# w076o.net
KiCad netlist of a schematic drawn in EAGLE
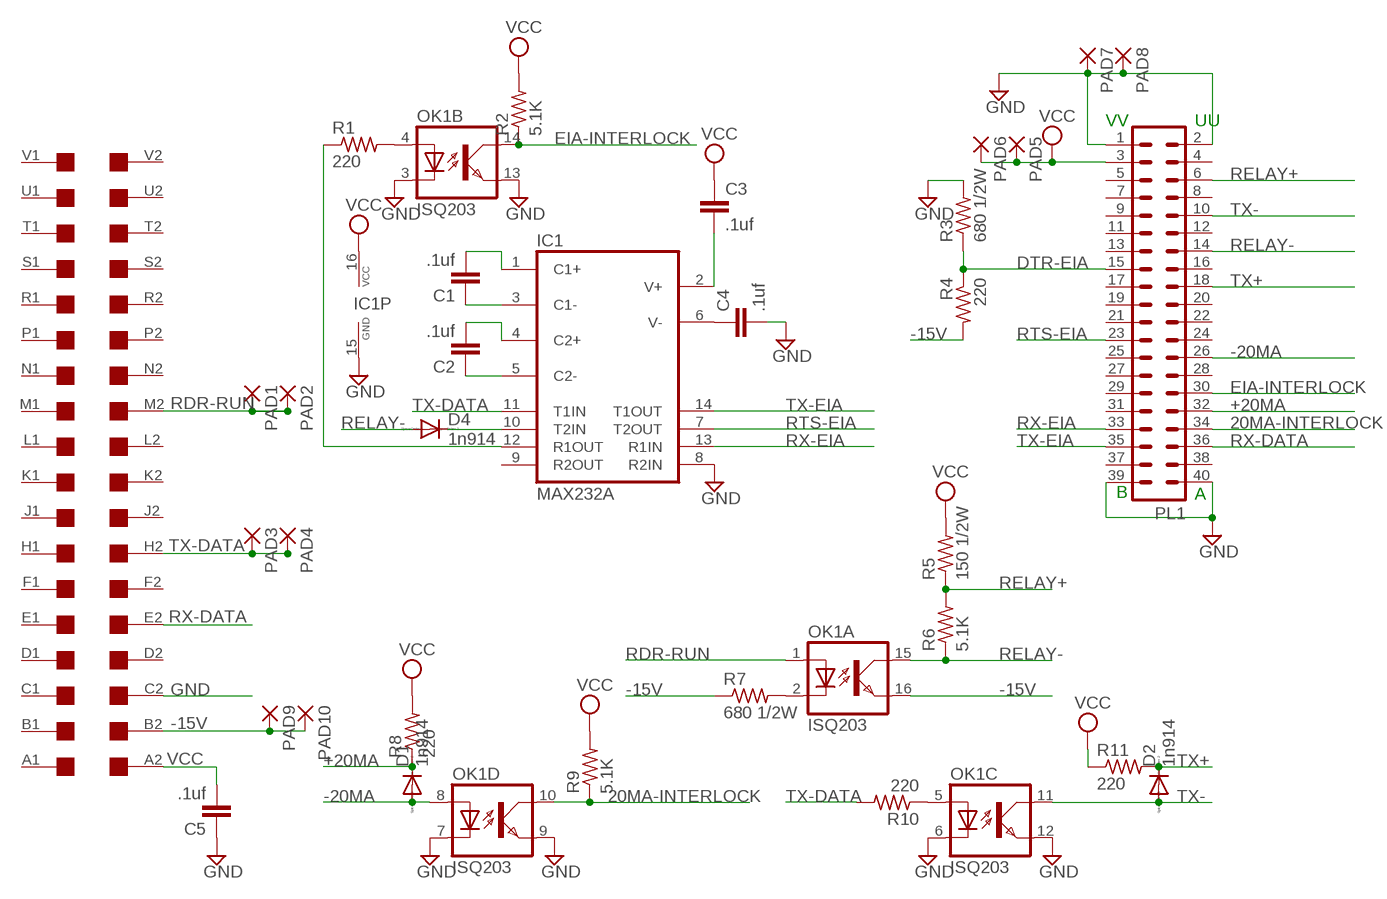
[diagram p0: schematic, sheet 1]

(export (version "E")
  (design (tool "Eeschema 10.0.6"))
  (components
    (comp (ref "C1")
      (value ".1uf")
      (footprint "eagle-import:C050-025X075")
      (libsource (lib "eagle-import") (part "C-EU050-025X075"))
    )
    (comp (ref "C2")
      (value ".1uf")
      (footprint "eagle-import:C050-025X075")
      (libsource (lib "eagle-import") (part "C-EU050-025X075"))
    )
    (comp (ref "C3")
      (value ".1uf")
      (footprint "eagle-import:C050-025X075")
      (libsource (lib "eagle-import") (part "C-EU050-025X075"))
    )
    (comp (ref "C4")
      (value ".1uf")
      (footprint "eagle-import:C050-025X075")
      (libsource (lib "eagle-import") (part "C-EU050-025X075"))
    )
    (comp (ref "C5")
      (value ".1uf")
      (footprint "eagle-import:C050-025X075")
      (libsource (lib "eagle-import") (part "C-EU050-025X075"))
    )
    (comp (ref "D1")
      (value "1n914")
      (footprint "eagle-import:DO41-10")
      (libsource (lib "eagle-import") (part "1N4004"))
    )
    (comp (ref "D2")
      (value "1n914")
      (footprint "eagle-import:DO41-10")
      (libsource (lib "eagle-import") (part "1N4004"))
    )
    (comp (ref "D4")
      (value "1n914")
      (footprint "eagle-import:DO41-10")
      (libsource (lib "eagle-import") (part "1N4004"))
    )
    (comp (ref "IC1")
      (value "MAX232A")
      (footprint "eagle-import:DIL16")
      (fields (field (name "MF") "MAXIM") (field (name "MPN") "MAX232ACPE+"))
      (libsource (lib "eagle-import") (part "MAX232"))
    )
    (comp (ref "OK1")
      (value "ISQ203")
      (footprint "eagle-import:DIL16")
      (fields (field (name "MF") "VISHAY/TELEFUNKEN") (field (name "MPN") "ILQ1"))
      (libsource (lib "eagle-import") (part "ILQ1"))
    )
    (comp (ref "PAD1")
      (value "1,6/0,8")
      (footprint "eagle-import:1,6_0,8")
      (libsource (lib "eagle-import") (part "1,6/0,8"))
    )
    (comp (ref "PAD2")
      (value "1,6/0,8")
      (footprint "eagle-import:1,6_0,8")
      (libsource (lib "eagle-import") (part "1,6/0,8"))
    )
    (comp (ref "PAD3")
      (value "1,6/0,8")
      (footprint "eagle-import:1,6_0,8")
      (libsource (lib "eagle-import") (part "1,6/0,8"))
    )
    (comp (ref "PAD4")
      (value "1,6/0,8")
      (footprint "eagle-import:1,6_0,8")
      (libsource (lib "eagle-import") (part "1,6/0,8"))
    )
    (comp (ref "PAD5")
      (value "1,6/0,8")
      (footprint "eagle-import:1,6_0,8")
      (libsource (lib "eagle-import") (part "1,6/0,8"))
    )
    (comp (ref "PAD6")
      (value "1,6/0,8")
      (footprint "eagle-import:1,6_0,8")
      (libsource (lib "eagle-import") (part "1,6/0,8"))
    )
    (comp (ref "PAD7")
      (value "1,6/0,8")
      (footprint "eagle-import:1,6_0,8")
      (libsource (lib "eagle-import") (part "1,6/0,8"))
    )
    (comp (ref "PAD8")
      (value "1,6/0,8")
      (footprint "eagle-import:1,6_0,8")
      (libsource (lib "eagle-import") (part "1,6/0,8"))
    )
    (comp (ref "PAD9")
      (value "1,6/0,8")
      (footprint "eagle-import:1,6_0,8")
      (libsource (lib "eagle-import") (part "1,6/0,8"))
    )
    (comp (ref "PAD10")
      (value "1,6/0,8")
      (footprint "eagle-import:1,6_0,8")
      (libsource (lib "eagle-import") (part "1,6/0,8"))
    )
    (comp (ref "PL1")
      (value "40H")
      (footprint "eagle-import:40H")
      (libsource (lib "eagle-import") (part "40H"))
    )
    (comp (ref "R1")
      (value "220")
      (footprint "eagle-import:0207_10")
      (libsource (lib "eagle-import") (part "R-US_0207/10"))
    )
    (comp (ref "R2")
      (value "5.1K")
      (footprint "eagle-import:0207_10")
      (libsource (lib "eagle-import") (part "R-US_0207/10"))
    )
    (comp (ref "R3")
      (value "680 1/2W")
      (footprint "eagle-import:0207_12")
      (libsource (lib "eagle-import") (part "R-US_0207/12"))
    )
    (comp (ref "R4")
      (value "220")
      (footprint "eagle-import:0207_10")
      (libsource (lib "eagle-import") (part "R-US_0207/10"))
    )
    (comp (ref "R5")
      (value "150 1/2W")
      (footprint "eagle-import:0207_12")
      (libsource (lib "eagle-import") (part "R-US_0207/12"))
    )
    (comp (ref "R6")
      (value "5.1K")
      (footprint "eagle-import:0207_10")
      (libsource (lib "eagle-import") (part "R-US_0207/10"))
    )
    (comp (ref "R7")
      (value "680 1/2W")
      (footprint "eagle-import:0207_12")
      (libsource (lib "eagle-import") (part "R-US_0207/12"))
    )
    (comp (ref "R8")
      (value "220")
      (footprint "eagle-import:0207_10")
      (libsource (lib "eagle-import") (part "R-US_0207/10"))
    )
    (comp (ref "R9")
      (value "5.1K")
      (footprint "eagle-import:0207_10")
      (libsource (lib "eagle-import") (part "R-US_0207/10"))
    )
    (comp (ref "R10")
      (value "220")
      (footprint "eagle-import:0207_10")
      (libsource (lib "eagle-import") (part "R-US_0207/10"))
    )
    (comp (ref "R11")
      (value "220")
      (footprint "eagle-import:0207_10")
      (libsource (lib "eagle-import") (part "R-US_0207/10"))
    )
    (comp (ref "U$1")
      (value "DEC-FLIPCHIP")
      (footprint "eagle-import:DEC-FLIPCHIP")
      (libsource (lib "eagle-import") (part "DEC-FLIPCHIP"))
    )
  )
  (nets
    (net (code "1") (name "/+20MA") (class "Default")
      (node (ref "D1") (pin "C") (pinfunction "C_C") (pintype "passive"))
      (node (ref "PL1") (pin "32") (pinfunction "32_32") (pintype "passive"))
      (node (ref "R8") (pin "1") (pinfunction "1_1") (pintype "passive"))
    )
    (net (code "2") (name "/-15V") (class "Default")
      (node (ref "OK1") (pin "16") (pinfunction "EMIT_16") (pintype "passive"))
      (node (ref "PAD10") (pin "1") (pinfunction "P_1") (pintype "passive"))
      (node (ref "PAD9") (pin "1") (pinfunction "P_1") (pintype "passive"))
      (node (ref "R4") (pin "2") (pinfunction "2_2") (pintype "passive"))
      (node (ref "R7") (pin "1") (pinfunction "1_1") (pintype "passive"))
      (node (ref "U$1") (pin "B2") (pinfunction "B2_B2") (pintype "passive"))
    )
    (net (code "3") (name "/-20MA") (class "Default")
      (node (ref "D1") (pin "A") (pinfunction "A_A") (pintype "passive"))
      (node (ref "OK1") (pin "8") (pinfunction "A_8") (pintype "passive"))
      (node (ref "PL1") (pin "26") (pinfunction "26_26") (pintype "passive"))
    )
    (net (code "4") (name "/20MA-INTERLOCK") (class "Default")
      (node (ref "OK1") (pin "10") (pinfunction "COL_10") (pintype "passive"))
      (node (ref "PL1") (pin "34") (pinfunction "34_34") (pintype "passive"))
      (node (ref "R9") (pin "1") (pinfunction "1_1") (pintype "passive"))
    )
    (net (code "5") (name "/DTR-EIA") (class "Default")
      (node (ref "PL1") (pin "15") (pinfunction "15_15") (pintype "passive"))
      (node (ref "R3") (pin "1") (pinfunction "1_1") (pintype "passive"))
      (node (ref "R4") (pin "1") (pinfunction "1_1") (pintype "passive"))
    )
    (net (code "6") (name "/EIA-INTERLOCK") (class "Default")
      (node (ref "OK1") (pin "14") (pinfunction "COL_14") (pintype "passive"))
      (node (ref "PL1") (pin "30") (pinfunction "30_30") (pintype "passive"))
      (node (ref "R2") (pin "1") (pinfunction "1_1") (pintype "passive"))
    )
    (net (code "7") (name "/RDR-RUN") (class "Default")
      (node (ref "OK1") (pin "1") (pinfunction "A_1") (pintype "passive"))
      (node (ref "PAD1") (pin "1") (pinfunction "P_1") (pintype "passive"))
      (node (ref "PAD2") (pin "1") (pinfunction "P_1") (pintype "passive"))
      (node (ref "U$1") (pin "M2") (pinfunction "M2_M2") (pintype "passive"))
    )
    (net (code "8") (name "/RELAY+") (class "Default")
      (node (ref "PL1") (pin "6") (pinfunction "6_6") (pintype "passive"))
      (node (ref "R5") (pin "1") (pinfunction "1_1") (pintype "passive"))
      (node (ref "R6") (pin "2") (pinfunction "2_2") (pintype "passive"))
    )
    (net (code "9") (name "/RELAY-") (class "Default")
      (node (ref "D4") (pin "A") (pinfunction "A_A") (pintype "passive"))
      (node (ref "OK1") (pin "15") (pinfunction "COL_15") (pintype "passive"))
      (node (ref "PL1") (pin "14") (pinfunction "14_14") (pintype "passive"))
      (node (ref "R6") (pin "1") (pinfunction "1_1") (pintype "passive"))
    )
    (net (code "10") (name "/RTS-EIA") (class "Default")
      (node (ref "IC1") (pin "7") (pinfunction "T2OUT_7") (pintype "output"))
      (node (ref "PL1") (pin "23") (pinfunction "23_23") (pintype "passive"))
    )
    (net (code "11") (name "/RX-DATA") (class "Default")
      (node (ref "PL1") (pin "36") (pinfunction "36_36") (pintype "passive"))
      (node (ref "U$1") (pin "E2") (pinfunction "E2_E2") (pintype "passive"))
    )
    (net (code "12") (name "/RX-EIA") (class "Default")
      (node (ref "IC1") (pin "13") (pinfunction "R1IN_13") (pintype "input"))
      (node (ref "PL1") (pin "33") (pinfunction "33_33") (pintype "passive"))
    )
    (net (code "13") (name "/TX+") (class "Default")
      (node (ref "D2") (pin "C") (pinfunction "C_C") (pintype "passive"))
      (node (ref "PL1") (pin "18") (pinfunction "18_18") (pintype "passive"))
      (node (ref "R11") (pin "2") (pinfunction "2_2") (pintype "passive"))
    )
    (net (code "14") (name "/TX-") (class "Default")
      (node (ref "D2") (pin "A") (pinfunction "A_A") (pintype "passive"))
      (node (ref "OK1") (pin "11") (pinfunction "COL_11") (pintype "passive"))
      (node (ref "PL1") (pin "10") (pinfunction "10_10") (pintype "passive"))
    )
    (net (code "15") (name "/TX-DATA") (class "Default")
      (node (ref "IC1") (pin "11") (pinfunction "T1IN_11") (pintype "input"))
      (node (ref "PAD3") (pin "1") (pinfunction "P_1") (pintype "passive"))
      (node (ref "PAD4") (pin "1") (pinfunction "P_1") (pintype "passive"))
      (node (ref "R10") (pin "2") (pinfunction "2_2") (pintype "passive"))
      (node (ref "U$1") (pin "H2") (pinfunction "H2_H2") (pintype "passive"))
    )
    (net (code "16") (name "/TX-EIA") (class "Default")
      (node (ref "IC1") (pin "14") (pinfunction "T1OUT_14") (pintype "output"))
      (node (ref "PL1") (pin "35") (pinfunction "35_35") (pintype "passive"))
    )
    (net (code "17") (name "GND") (class "Default")
      (node (ref "C4") (pin "2") (pinfunction "2_2") (pintype "passive"))
      (node (ref "C5") (pin "1") (pinfunction "1_1") (pintype "passive"))
      (node (ref "IC1") (pin "15") (pinfunction "GND_15") (pintype "power_in"))
      (node (ref "IC1") (pin "8") (pinfunction "R2IN_8") (pintype "input"))
      (node (ref "OK1") (pin "12") (pinfunction "EMIT_12") (pintype "passive"))
      (node (ref "OK1") (pin "13") (pinfunction "EMIT_13") (pintype "passive"))
      (node (ref "OK1") (pin "3") (pinfunction "C_3") (pintype "passive"))
      (node (ref "OK1") (pin "6") (pinfunction "C_6") (pintype "passive"))
      (node (ref "OK1") (pin "7") (pinfunction "C_7") (pintype "passive"))
      (node (ref "OK1") (pin "9") (pinfunction "EMIT_9") (pintype "passive"))
      (node (ref "PAD7") (pin "1") (pinfunction "P_1") (pintype "passive"))
      (node (ref "PAD8") (pin "1") (pinfunction "P_1") (pintype "passive"))
      (node (ref "PL1") (pin "1") (pinfunction "1_1") (pintype "passive"))
      (node (ref "PL1") (pin "2") (pinfunction "2_2") (pintype "passive"))
      (node (ref "PL1") (pin "39") (pinfunction "39_39") (pintype "passive"))
      (node (ref "PL1") (pin "40") (pinfunction "40_40") (pintype "passive"))
      (node (ref "R3") (pin "2") (pinfunction "2_2") (pintype "passive"))
      (node (ref "U$1") (pin "C2") (pinfunction "C2_C2") (pintype "passive"))
    )
    (net (code "18") (name "Net-(IC1A-C1+)") (class "Default")
      (node (ref "C1") (pin "2") (pinfunction "2_2") (pintype "passive"))
      (node (ref "IC1") (pin "1") (pinfunction "C1+_1") (pintype "bidirectional"))
    )
    (net (code "19") (name "Net-(IC1A-C1-)") (class "Default")
      (node (ref "C1") (pin "1") (pinfunction "1_1") (pintype "passive"))
      (node (ref "IC1") (pin "3") (pinfunction "C1-_3") (pintype "bidirectional"))
    )
    (net (code "20") (name "Net-(IC1A-C2+)") (class "Default")
      (node (ref "C2") (pin "2") (pinfunction "2_2") (pintype "passive"))
      (node (ref "IC1") (pin "4") (pinfunction "C2+_4") (pintype "bidirectional"))
    )
    (net (code "21") (name "Net-(IC1A-C2-)") (class "Default")
      (node (ref "C2") (pin "1") (pinfunction "1_1") (pintype "passive"))
      (node (ref "IC1") (pin "5") (pinfunction "C2-_5") (pintype "bidirectional"))
    )
    (net (code "22") (name "Net-(IC1A-R1OUT)") (class "Default")
      (node (ref "IC1") (pin "12") (pinfunction "R1OUT_12") (pintype "output"))
      (node (ref "R1") (pin "1") (pinfunction "1_1") (pintype "passive"))
    )
    (net (code "23") (name "Net-(IC1A-T2IN)") (class "Default")
      (node (ref "D4") (pin "C") (pinfunction "C_C") (pintype "passive"))
      (node (ref "IC1") (pin "10") (pinfunction "T2IN_10") (pintype "input"))
    )
    (net (code "24") (name "Net-(IC1A-V+)") (class "Default")
      (node (ref "C3") (pin "2") (pinfunction "2_2") (pintype "passive"))
      (node (ref "IC1") (pin "2") (pinfunction "V+_2") (pintype "bidirectional"))
    )
    (net (code "25") (name "Net-(IC1A-V-)") (class "Default")
      (node (ref "C4") (pin "1") (pinfunction "1_1") (pintype "passive"))
      (node (ref "IC1") (pin "6") (pinfunction "V-_6") (pintype "bidirectional"))
    )
    (net (code "26") (name "Net-(OK1A-C)") (class "Default")
      (node (ref "OK1") (pin "2") (pinfunction "C_2") (pintype "passive"))
      (node (ref "R7") (pin "2") (pinfunction "2_2") (pintype "passive"))
    )
    (net (code "27") (name "Net-(OK1B-A)") (class "Default")
      (node (ref "OK1") (pin "4") (pinfunction "A_4") (pintype "passive"))
      (node (ref "R1") (pin "2") (pinfunction "2_2") (pintype "passive"))
    )
    (net (code "28") (name "Net-(OK1C-A)") (class "Default")
      (node (ref "OK1") (pin "5") (pinfunction "A_5") (pintype "passive"))
      (node (ref "R10") (pin "1") (pinfunction "1_1") (pintype "passive"))
    )
    (net (code "29") (name "VCC") (class "Default")
      (node (ref "C3") (pin "1") (pinfunction "1_1") (pintype "passive"))
      (node (ref "C5") (pin "2") (pinfunction "2_2") (pintype "passive"))
      (node (ref "IC1") (pin "16") (pinfunction "VCC_16") (pintype "power_in"))
      (node (ref "PAD5") (pin "1") (pinfunction "P_1") (pintype "passive"))
      (node (ref "PAD6") (pin "1") (pinfunction "P_1") (pintype "passive"))
      (node (ref "PL1") (pin "3") (pinfunction "3_3") (pintype "passive"))
      (node (ref "R11") (pin "1") (pinfunction "1_1") (pintype "passive"))
      (node (ref "R2") (pin "2") (pinfunction "2_2") (pintype "passive"))
      (node (ref "R5") (pin "2") (pinfunction "2_2") (pintype "passive"))
      (node (ref "R8") (pin "2") (pinfunction "2_2") (pintype "passive"))
      (node (ref "R9") (pin "2") (pinfunction "2_2") (pintype "passive"))
      (node (ref "U$1") (pin "A2") (pinfunction "A2_A2") (pintype "passive"))
    )
    (net (code "30") (name "unconnected-(IC1A-R2OUT-Pad9)") (class "Default")
      (node (ref "IC1") (pin "9") (pinfunction "R2OUT_9") (pintype "output"))
    )
    (net (code "31") (name "unconnected-(PL1-Pad4)") (class "Default")
      (node (ref "PL1") (pin "4") (pinfunction "4_4") (pintype "passive"))
    )
    (net (code "32") (name "unconnected-(PL1-Pad5)") (class "Default")
      (node (ref "PL1") (pin "5") (pinfunction "5_5") (pintype "passive"))
    )
    (net (code "33") (name "unconnected-(PL1-Pad7)") (class "Default")
      (node (ref "PL1") (pin "7") (pinfunction "7_7") (pintype "passive"))
    )
    (net (code "34") (name "unconnected-(PL1-Pad8)") (class "Default")
      (node (ref "PL1") (pin "8") (pinfunction "8_8") (pintype "passive"))
    )
    (net (code "35") (name "unconnected-(PL1-Pad9)") (class "Default")
      (node (ref "PL1") (pin "9") (pinfunction "9_9") (pintype "passive"))
    )
    (net (code "36") (name "unconnected-(PL1-Pad11)") (class "Default")
      (node (ref "PL1") (pin "11") (pinfunction "11_11") (pintype "passive"))
    )
    (net (code "37") (name "unconnected-(PL1-Pad12)") (class "Default")
      (node (ref "PL1") (pin "12") (pinfunction "12_12") (pintype "passive"))
    )
    (net (code "38") (name "unconnected-(PL1-Pad13)") (class "Default")
      (node (ref "PL1") (pin "13") (pinfunction "13_13") (pintype "passive"))
    )
    (net (code "39") (name "unconnected-(PL1-Pad16)") (class "Default")
      (node (ref "PL1") (pin "16") (pinfunction "16_16") (pintype "passive"))
    )
    (net (code "40") (name "unconnected-(PL1-Pad17)") (class "Default")
      (node (ref "PL1") (pin "17") (pinfunction "17_17") (pintype "passive"))
    )
    (net (code "41") (name "unconnected-(PL1-Pad19)") (class "Default")
      (node (ref "PL1") (pin "19") (pinfunction "19_19") (pintype "passive"))
    )
    (net (code "42") (name "unconnected-(PL1-Pad20)") (class "Default")
      (node (ref "PL1") (pin "20") (pinfunction "20_20") (pintype "passive"))
    )
    (net (code "43") (name "unconnected-(PL1-Pad21)") (class "Default")
      (node (ref "PL1") (pin "21") (pinfunction "21_21") (pintype "passive"))
    )
    (net (code "44") (name "unconnected-(PL1-Pad22)") (class "Default")
      (node (ref "PL1") (pin "22") (pinfunction "22_22") (pintype "passive"))
    )
    (net (code "45") (name "unconnected-(PL1-Pad24)") (class "Default")
      (node (ref "PL1") (pin "24") (pinfunction "24_24") (pintype "passive"))
    )
    (net (code "46") (name "unconnected-(PL1-Pad25)") (class "Default")
      (node (ref "PL1") (pin "25") (pinfunction "25_25") (pintype "passive"))
    )
    (net (code "47") (name "unconnected-(PL1-Pad27)") (class "Default")
      (node (ref "PL1") (pin "27") (pinfunction "27_27") (pintype "passive"))
    )
    (net (code "48") (name "unconnected-(PL1-Pad28)") (class "Default")
      (node (ref "PL1") (pin "28") (pinfunction "28_28") (pintype "passive"))
    )
    (net (code "49") (name "unconnected-(PL1-Pad29)") (class "Default")
      (node (ref "PL1") (pin "29") (pinfunction "29_29") (pintype "passive"))
    )
    (net (code "50") (name "unconnected-(PL1-Pad31)") (class "Default")
      (node (ref "PL1") (pin "31") (pinfunction "31_31") (pintype "passive"))
    )
    (net (code "51") (name "unconnected-(PL1-Pad37)") (class "Default")
      (node (ref "PL1") (pin "37") (pinfunction "37_37") (pintype "passive"))
    )
    (net (code "52") (name "unconnected-(PL1-Pad38)") (class "Default")
      (node (ref "PL1") (pin "38") (pinfunction "38_38") (pintype "passive"))
    )
    (net (code "53") (name "unconnected-(U$1-PadA1)") (class "Default")
      (node (ref "U$1") (pin "A1") (pinfunction "A1_A1") (pintype "passive"))
    )
    (net (code "54") (name "unconnected-(U$1-PadB1)") (class "Default")
      (node (ref "U$1") (pin "B1") (pinfunction "B1_B1") (pintype "passive"))
    )
    (net (code "55") (name "unconnected-(U$1-PadC1)") (class "Default")
      (node (ref "U$1") (pin "C1") (pinfunction "C1_C1") (pintype "passive"))
    )
    (net (code "56") (name "unconnected-(U$1-PadD1)") (class "Default")
      (node (ref "U$1") (pin "D1") (pinfunction "D1_D1") (pintype "passive"))
    )
    (net (code "57") (name "unconnected-(U$1-PadD2)") (class "Default")
      (node (ref "U$1") (pin "D2") (pinfunction "D2_D2") (pintype "passive"))
    )
    (net (code "58") (name "unconnected-(U$1-PadE1)") (class "Default")
      (node (ref "U$1") (pin "E1") (pinfunction "E1_E1") (pintype "passive"))
    )
    (net (code "59") (name "unconnected-(U$1-PadF1)") (class "Default")
      (node (ref "U$1") (pin "F1") (pinfunction "F1_F1") (pintype "passive"))
    )
    (net (code "60") (name "unconnected-(U$1-PadF2)") (class "Default")
      (node (ref "U$1") (pin "F2") (pinfunction "F2_F2") (pintype "passive"))
    )
    (net (code "61") (name "unconnected-(U$1-PadH1)") (class "Default")
      (node (ref "U$1") (pin "H1") (pinfunction "H1_H1") (pintype "passive"))
    )
    (net (code "62") (name "unconnected-(U$1-PadJ1)") (class "Default")
      (node (ref "U$1") (pin "J1") (pinfunction "J1_J1") (pintype "passive"))
    )
    (net (code "63") (name "unconnected-(U$1-PadJ2)") (class "Default")
      (node (ref "U$1") (pin "J2") (pinfunction "J2_J2") (pintype "passive"))
    )
    (net (code "64") (name "unconnected-(U$1-PadK1)") (class "Default")
      (node (ref "U$1") (pin "K1") (pinfunction "K1_K1") (pintype "passive"))
    )
    (net (code "65") (name "unconnected-(U$1-PadK2)") (class "Default")
      (node (ref "U$1") (pin "K2") (pinfunction "K2_K2") (pintype "passive"))
    )
    (net (code "66") (name "unconnected-(U$1-PadL1)") (class "Default")
      (node (ref "U$1") (pin "L1") (pinfunction "L1_L1") (pintype "passive"))
    )
    (net (code "67") (name "unconnected-(U$1-PadL2)") (class "Default")
      (node (ref "U$1") (pin "L2") (pinfunction "L2_L2") (pintype "passive"))
    )
    (net (code "68") (name "unconnected-(U$1-PadM1)") (class "Default")
      (node (ref "U$1") (pin "M1") (pinfunction "M1_M1") (pintype "passive"))
    )
    (net (code "69") (name "unconnected-(U$1-PadN1)") (class "Default")
      (node (ref "U$1") (pin "N1") (pinfunction "N1_N1") (pintype "passive"))
    )
    (net (code "70") (name "unconnected-(U$1-PadN2)") (class "Default")
      (node (ref "U$1") (pin "N2") (pinfunction "N2_N2") (pintype "passive"))
    )
    (net (code "71") (name "unconnected-(U$1-PadP1)") (class "Default")
      (node (ref "U$1") (pin "P1") (pinfunction "P1_P1") (pintype "passive"))
    )
    (net (code "72") (name "unconnected-(U$1-PadP2)") (class "Default")
      (node (ref "U$1") (pin "P2") (pinfunction "P2_P2") (pintype "passive"))
    )
    (net (code "73") (name "unconnected-(U$1-PadR1)") (class "Default")
      (node (ref "U$1") (pin "R1") (pinfunction "R1_R1") (pintype "passive"))
    )
    (net (code "74") (name "unconnected-(U$1-PadR2)") (class "Default")
      (node (ref "U$1") (pin "R2") (pinfunction "R2_R2") (pintype "passive"))
    )
    (net (code "75") (name "unconnected-(U$1-PadS1)") (class "Default")
      (node (ref "U$1") (pin "S1") (pinfunction "S1_S1") (pintype "passive"))
    )
    (net (code "76") (name "unconnected-(U$1-PadS2)") (class "Default")
      (node (ref "U$1") (pin "S2") (pinfunction "S2_S2") (pintype "passive"))
    )
    (net (code "77") (name "unconnected-(U$1-PadT1)") (class "Default")
      (node (ref "U$1") (pin "T1") (pinfunction "T1_T1") (pintype "passive"))
    )
    (net (code "78") (name "unconnected-(U$1-PadT2)") (class "Default")
      (node (ref "U$1") (pin "T2") (pinfunction "T2_T2") (pintype "passive"))
    )
    (net (code "79") (name "unconnected-(U$1-PadU1)") (class "Default")
      (node (ref "U$1") (pin "U1") (pinfunction "U1_U1") (pintype "passive"))
    )
    (net (code "80") (name "unconnected-(U$1-PadU2)") (class "Default")
      (node (ref "U$1") (pin "U2") (pinfunction "U2_U2") (pintype "passive"))
    )
    (net (code "81") (name "unconnected-(U$1-PadV1)") (class "Default")
      (node (ref "U$1") (pin "V1") (pinfunction "V1_V1") (pintype "passive"))
    )
    (net (code "82") (name "unconnected-(U$1-PadV2)") (class "Default")
      (node (ref "U$1") (pin "V2") (pinfunction "V2_V2") (pintype "passive"))
    )
  )
)
